# QSPIFlash.net
KiCad netlist of a schematic drawn in Altium Designer
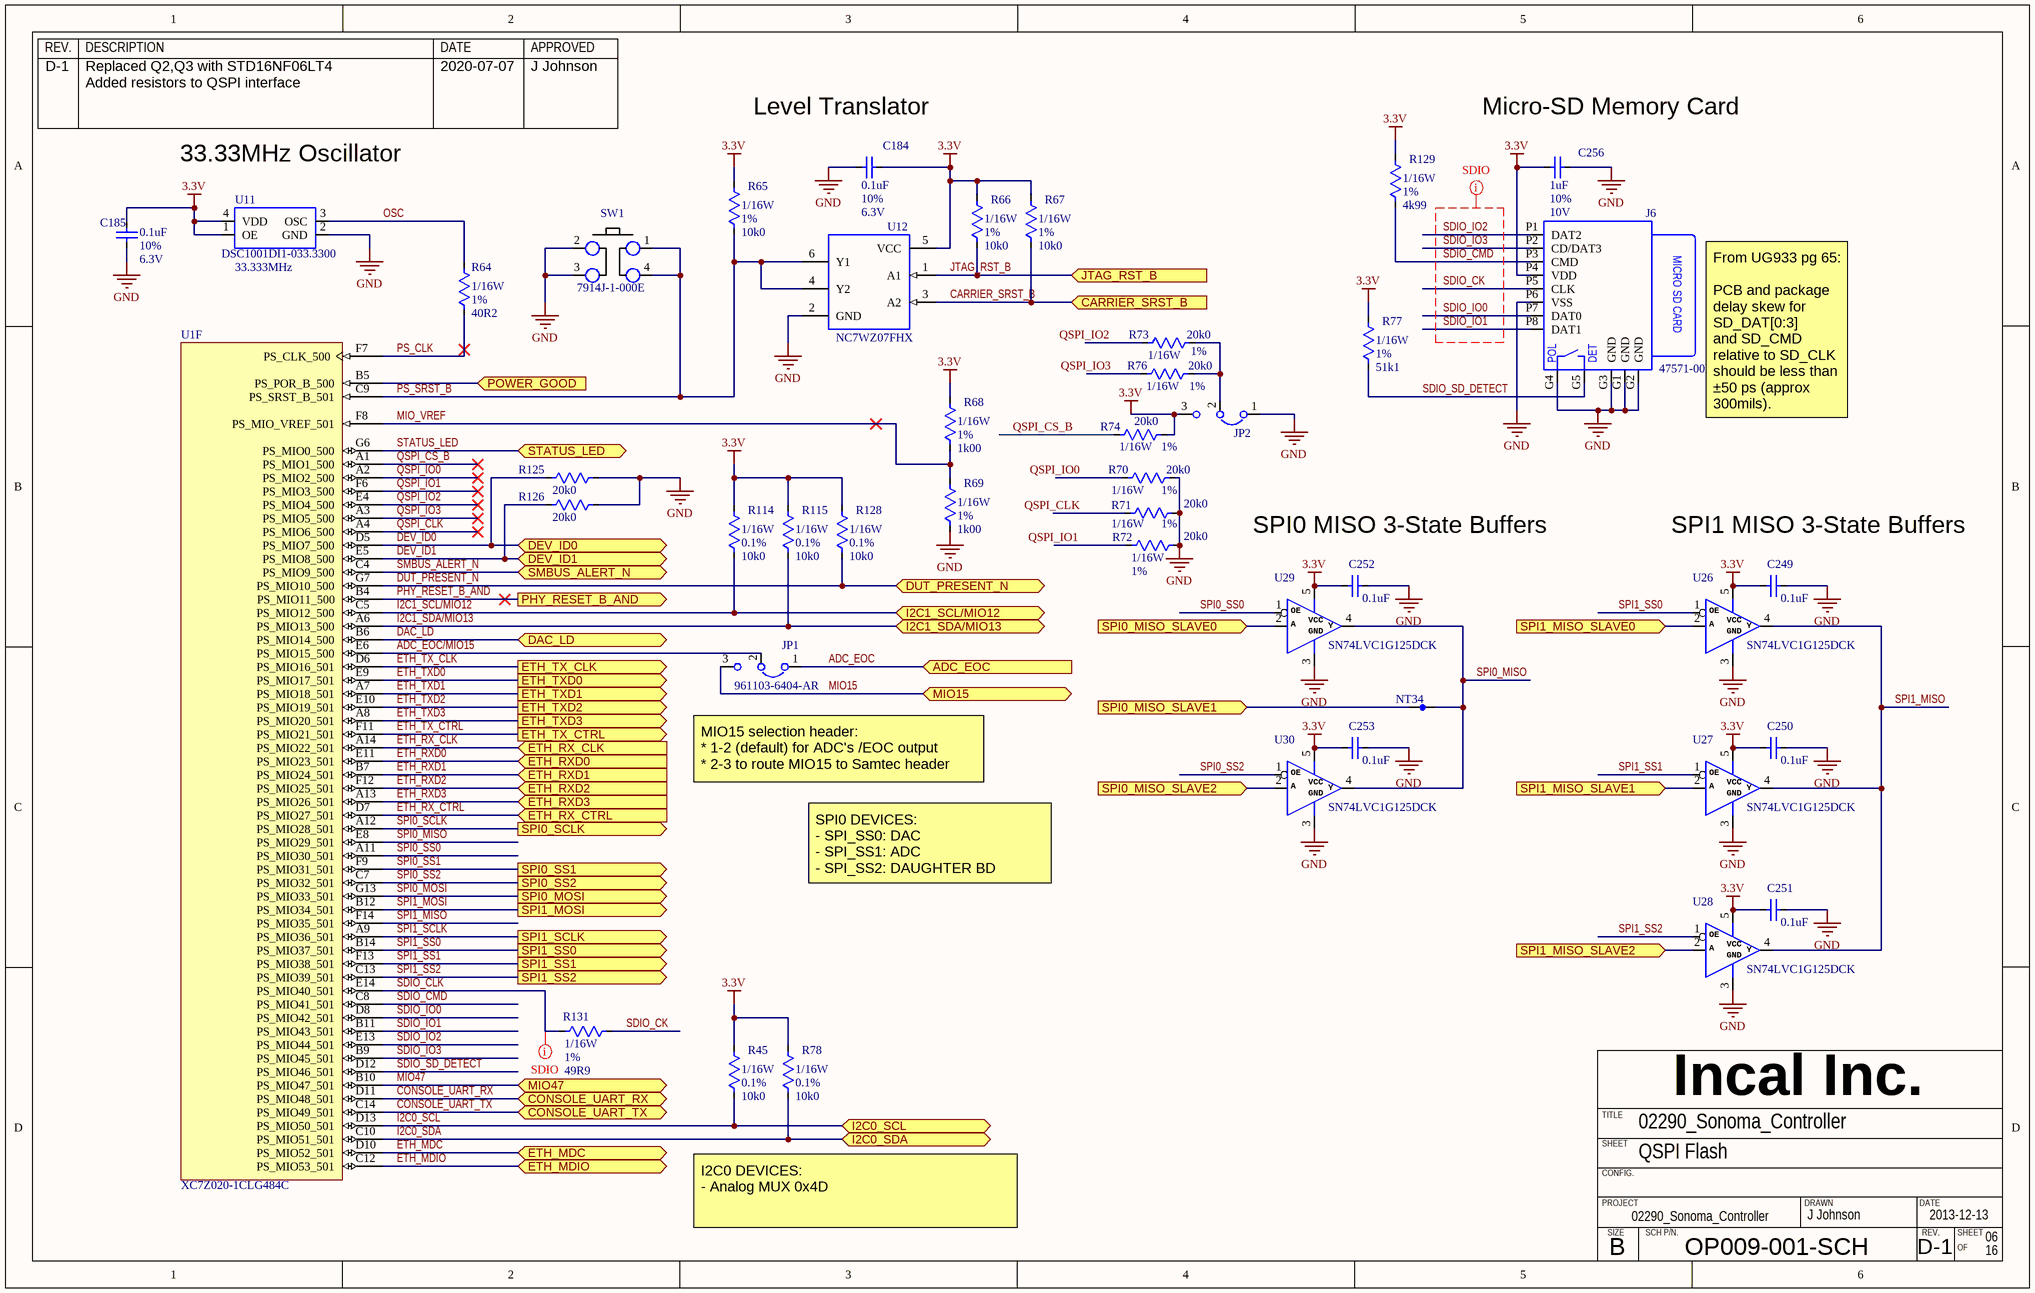
[diagram p0: QSPIFlash.SchDoc]

(export (version "E")
  (design (tool "Eeschema 10.0.6"))
  (components
    (comp (ref "C184")
      (value "0.1uF")
      (footprint "CAPC0603X33N")
      (description "Capacitor ceramic, X5R, 0.1uF, 6.3V, 10%, -55 to +125 C, EIA0201")
      (fields
        (field (name "TOLERANCE") "10%")
        (field (name "VOLTAGE") "6.3V")
        (field (name "Comment") "CAPACITOR_NP_TYPE1")
      )
      (libsource (lib "parts") (part "CAPACITOR_NP_TYPE1"))
    )
    (comp (ref "C185")
      (value "0.1uF")
      (footprint "CAPC0603X33N")
      (description "Capacitor ceramic, X5R, 0.1uF, 6.3V, 10%, -55 to +125 C, EIA0201")
      (fields
        (field (name "TOLERANCE") "10%")
        (field (name "VOLTAGE") "6.3V")
        (field (name "Comment") "CAPACITOR_NP_TYPE1")
      )
      (libsource (lib "parts") (part "CAPACITOR_NP_TYPE1"))
    )
    (comp (ref "C249")
      (value "0.1uF")
      (footprint "CAPC0603X33N")
      (description "Capacitor ceramic, X5R, 0.1uF, 6.3V, 10%, -55 to +125 C, EIA0201")
      (fields (field (name "TOLERANCE") "10%") (field (name "VOLTAGE") "6.3V"))
      (libsource (lib "parts") (part "CAPACITOR_NP_TYPE1"))
    )
    (comp (ref "C250")
      (value "0.1uF")
      (footprint "CAPC0603X33N")
      (description "Capacitor ceramic, X5R, 0.1uF, 6.3V, 10%, -55 to +125 C, EIA0201")
      (fields (field (name "TOLERANCE") "10%") (field (name "VOLTAGE") "6.3V"))
      (libsource (lib "parts") (part "CAPACITOR_NP_TYPE1"))
    )
    (comp (ref "C251")
      (value "0.1uF")
      (footprint "CAPC0603X33N")
      (description "Capacitor ceramic, X5R, 0.1uF, 6.3V, 10%, -55 to +125 C, EIA0201")
      (fields (field (name "TOLERANCE") "10%") (field (name "VOLTAGE") "6.3V"))
      (libsource (lib "parts") (part "CAPACITOR_NP_TYPE1"))
    )
    (comp (ref "C252")
      (value "0.1uF")
      (footprint "CAPC0603X33N")
      (description "Capacitor ceramic, X5R, 0.1uF, 6.3V, 10%, -55 to +125 C, EIA0201")
      (fields (field (name "TOLERANCE") "10%") (field (name "VOLTAGE") "6.3V"))
      (libsource (lib "parts") (part "CAPACITOR_NP_TYPE1"))
    )
    (comp (ref "C253")
      (value "0.1uF")
      (footprint "CAPC0603X33N")
      (description "Capacitor ceramic, X5R, 0.1uF, 6.3V, 10%, -55 to +125 C, EIA0201")
      (fields (field (name "TOLERANCE") "10%") (field (name "VOLTAGE") "6.3V"))
      (libsource (lib "parts") (part "CAPACITOR_NP_TYPE1"))
    )
    (comp (ref "C256")
      (value "1uF")
      (footprint "CAPC1005X33N")
      (description "Capacitor ceramic, X5R, 1uF, 10V, 10%, -55 to +85 C, EIA0402")
      (fields
        (field (name "TOLERANCE") "10%")
        (field (name "VOLTAGE") "10V")
        (field (name "Comment") "CAPACITOR_NP_TYPE1")
      )
      (libsource (lib "parts") (part "CAPACITOR_NP_TYPE1"))
    )
    (comp (ref "J6")
      (value "SD_MICRO_DET1")
      (footprint "47571-0001")
      (description "MicroSD Card Header with Detect, 9 pin, RA, 1.10 mm, SMT, -40 to +85C")
      (fields
        (field (name "POWER") "Pow")
        (field (name "VOLTAGE") "Vol")
        (field (name "MFG PART NUMBER 1") "47571-0001")
      )
      (libsource (lib "parts") (part "SD_MICRO_DET1"))
    )
    (comp (ref "JP1")
      (value "JP_HDR3x1_DEF1")
      (footprint "JMPR3P254_SHUNT12")
      (description "Jumper Header .100'', 3-pin, Default position 1-2, TH")
      (fields
        (field (name "POWER") "Pow")
        (field (name "VOLTAGE") "Vol")
        (field (name "MFG PART NUMBER 1") "961103-6404-AR")
      )
      (libsource (lib "parts") (part "JP_HDR3x1_DEF1"))
    )
    (comp (ref "JP2")
      (value "JP_HDR3x1_DEF1")
      (footprint "JMPR3P254_SHUNT12")
      (description "Jumper Header 100mil, 3-pin, Default position 1-2, TH")
      (libsource (lib "parts") (part "JP_HDR3x1_DEF1"))
    )
    (comp (ref "NT34")
      (value "NET_TIE_1X1")
      (footprint "NET_TIE_1X1")
      (description "Net Tie 1 to 1")
      (libsource (lib "parts") (part "NET_TIE_1X1"))
    )
    (comp (ref "R45")
      (value "10k0")
      (footprint "RESC1005X33N")
      (description "Resistor, 10k0, 1/16W, 0.1%, -50 to +155 C, EIA0402")
      (fields (field (name "VOLTAGE") "50V") (field (name "POWER") "1/16W") (field (name "TOLERANCE") "0.1%"))
      (libsource (lib "parts") (part "RESISTOR_TYPE1"))
    )
    (comp (ref "R64")
      (value "40R2")
      (footprint "RESC1005X33N")
      (description "Resistor, 40R2, 1/16W, 1%, -50 to +155 C, EIA0402, EIA(M)1005")
      (fields (field (name "VOLTAGE") "50V") (field (name "POWER") "1/16W") (field (name "TOLERANCE") "1%"))
      (libsource (lib "parts") (part "RESISTOR_TYPE1"))
    )
    (comp (ref "R65")
      (value "10k0")
      (footprint "RESC1005X33N")
      (description "Resistor, 10k0, 1/16W, 1%, -55 to +155 C, EIA0402")
      (fields (field (name "VOLTAGE") "50V") (field (name "POWER") "1/16W") (field (name "TOLERANCE") "1%"))
      (libsource (lib "parts") (part "RESISTOR_TYPE1"))
    )
    (comp (ref "R66")
      (value "10k0")
      (footprint "RESC1005X33N")
      (description "Resistor, 10k0, 1/16W, 1%, -55 to +155 C, EIA0402")
      (fields (field (name "VOLTAGE") "50V") (field (name "POWER") "1/16W") (field (name "TOLERANCE") "1%"))
      (libsource (lib "parts") (part "RESISTOR_TYPE1"))
    )
    (comp (ref "R67")
      (value "10k0")
      (footprint "RESC1005X33N")
      (description "Resistor, 10k0, 1/16W, 1%, -55 to +155 C, EIA0402")
      (fields (field (name "VOLTAGE") "50V") (field (name "POWER") "1/16W") (field (name "TOLERANCE") "1%"))
      (libsource (lib "parts") (part "RESISTOR_TYPE1"))
    )
    (comp (ref "R68")
      (value "1k00")
      (footprint "RESC1005X33N")
      (description "Resistor, 1k00, 1/16W, 1%, -55 to +155 C, EIA0402")
      (fields (field (name "VOLTAGE") "50V") (field (name "POWER") "1/16W") (field (name "TOLERANCE") "1%"))
      (libsource (lib "parts") (part "RESISTOR_TYPE1"))
    )
    (comp (ref "R69")
      (value "1k00")
      (footprint "RESC1005X33N")
      (description "Resistor, 1k00, 1/16W, 1%, -55 to +155 C, EIA0402")
      (fields (field (name "VOLTAGE") "50V") (field (name "POWER") "1/16W") (field (name "TOLERANCE") "1%"))
      (libsource (lib "parts") (part "RESISTOR_TYPE1"))
    )
    (comp (ref "R70")
      (value "20k0")
      (footprint "RESC1005X33N")
      (description "Resistor, 20k0, 1%, 1/16W, 0402")
      (fields (field (name "VOLTAGE") "50V") (field (name "POWER") "1/16W") (field (name "TOLERANCE") "1%"))
      (libsource (lib "parts") (part "RESISTOR_TYPE1"))
    )
    (comp (ref "R71")
      (value "20k0")
      (footprint "RESC1005X33N")
      (description "Resistor, 20k0, 1%, 1/16W, 0402")
      (fields (field (name "VOLTAGE") "50V") (field (name "POWER") "1/16W") (field (name "TOLERANCE") "1%"))
      (libsource (lib "parts") (part "RESISTOR_TYPE1"))
    )
    (comp (ref "R72")
      (value "20k0")
      (footprint "RESC1005X33N")
      (description "Resistor, 20k0, 1%, 1/16W, 0402")
      (fields (field (name "VOLTAGE") "50V") (field (name "POWER") "1/16W") (field (name "TOLERANCE") "1%"))
      (libsource (lib "parts") (part "RESISTOR_TYPE1"))
    )
    (comp (ref "R73")
      (value "20k0")
      (footprint "RESC1005X33N")
      (description "Resistor, 20k0, 1%, 1/16W, 0402")
      (fields (field (name "VOLTAGE") "50V") (field (name "POWER") "1/16W") (field (name "TOLERANCE") "1%"))
      (libsource (lib "parts") (part "RESISTOR_TYPE1"))
    )
    (comp (ref "R74")
      (value "20k0")
      (footprint "RESC1005X33N")
      (description "Resistor, 20k0, 1%, 1/16W, 0402")
      (fields (field (name "VOLTAGE") "50V") (field (name "POWER") "1/16W") (field (name "TOLERANCE") "1%"))
      (libsource (lib "parts") (part "RESISTOR_TYPE1"))
    )
    (comp (ref "R76")
      (value "20k0")
      (footprint "RESC1005X33N")
      (description "Resistor, 20k0, 1%, 1/16W, 0402")
      (fields (field (name "VOLTAGE") "50V") (field (name "POWER") "1/16W") (field (name "TOLERANCE") "1%"))
      (libsource (lib "parts") (part "RESISTOR_TYPE1"))
    )
    (comp (ref "R77")
      (value "51k1")
      (footprint "RESC1005X33N")
      (description "Resistor, 51k1, 1/16W, 1%, -50 to +155 C, EIA0402, EIA(M)1005")
      (fields (field (name "VOLTAGE") "50V") (field (name "POWER") "1/16W") (field (name "TOLERANCE") "1%"))
      (libsource (lib "parts") (part "RESISTOR_TYPE1"))
    )
    (comp (ref "R78")
      (value "10k0")
      (footprint "RESC1005X33N")
      (description "Resistor, 10k0, 1/16W, 0.1%, -50 to +155 C, EIA0402")
      (fields (field (name "VOLTAGE") "50V") (field (name "POWER") "1/16W") (field (name "TOLERANCE") "0.1%"))
      (libsource (lib "parts") (part "RESISTOR_TYPE1"))
    )
    (comp (ref "R114")
      (value "10k0")
      (footprint "RESC1005X33N")
      (description "Resistor, 10k0, 1/16W, 0.1%, -50 to +155 C, EIA0402")
      (fields (field (name "VOLTAGE") "50V") (field (name "POWER") "1/16W") (field (name "TOLERANCE") "0.1%"))
      (libsource (lib "parts") (part "RESISTOR_TYPE1"))
    )
    (comp (ref "R115")
      (value "10k0")
      (footprint "RESC1005X33N")
      (description "Resistor, 10k0, 1/16W, 0.1%, -50 to +155 C, EIA0402")
      (fields (field (name "VOLTAGE") "50V") (field (name "POWER") "1/16W") (field (name "TOLERANCE") "0.1%"))
      (libsource (lib "parts") (part "RESISTOR_TYPE1"))
    )
    (comp (ref "R125")
      (value "20k0")
      (footprint "RESC1005X33N")
      (description "Resistor, 20k0, 1/16W, 1%, -50 to +155 C, EIA0402, EIA(M)1005")
      (fields (field (name "VOLTAGE") "50V") (field (name "POWER") "1/16W"))
      (libsource (lib "parts") (part "RESISTOR_TYPE1"))
    )
    (comp (ref "R126")
      (value "20k0")
      (footprint "RESC1005X33N")
      (description "Resistor, 20k0, 1/16W, 1%, -50 to +155 C, EIA0402, EIA(M)1005")
      (fields (field (name "VOLTAGE") "50V") (field (name "POWER") "1/16W"))
      (libsource (lib "parts") (part "RESISTOR_TYPE1"))
    )
    (comp (ref "R128")
      (value "10k0")
      (footprint "RESC1005X33N")
      (description "Resistor, 10k0, 1/16W, 0.1%, -50 to +155 C, EIA0402")
      (fields (field (name "VOLTAGE") "50V") (field (name "POWER") "1/16W") (field (name "TOLERANCE") "0.1%"))
      (libsource (lib "parts") (part "RESISTOR_TYPE1"))
    )
    (comp (ref "R129")
      (value "4k99")
      (footprint "RESC1005X33N")
      (description "Resistor, 4k99, 1/16W, 1%, -50 to +155 C, EIA0402, EIA(M)1005")
      (fields (field (name "VOLTAGE") "50V") (field (name "POWER") "1/16W") (field (name "TOLERANCE") "1%"))
      (libsource (lib "parts") (part "RESISTOR_TYPE1"))
    )
    (comp (ref "R131")
      (value "49R9")
      (footprint "RESC1005X33N")
      (description "Resistor, 49R9, 1%, 1/16W, 0402, 0402")
      (fields (field (name "VOLTAGE") "50V") (field (name "POWER") "1/16W") (field (name "TOLERANCE") "1%"))
      (libsource (lib "parts") (part "RESISTOR_TYPE1"))
    )
    (comp (ref "SW1")
      (value "7914J-1-000E")
      (footprint "7914J-1-000E")
      (description "Switch, tactile, 39V, 4mm, -55 to +125 C, SMD")
      (fields (field (name "POWER") "Pow") (field (name "VOLTAGE") "39V"))
      (libsource (lib "parts") (part "SW_SPST_TYPE1"))
    )
    (comp (ref "U1")
      (value "XC7Z020-1CLG484C")
      (footprint "CLG484")
      (description "667 MHz Zynq™-7000 AP SoC, 130 PS I/O, 200 FPGA I/O, 484-Ball BGA, Speed Grade 1, Commercial Grade")
      (fields (field (name "GENERIC PART NUMBER") "XC7Z020") (field (name "MANUFACTURER") "Xilinx"))
      (libsource (lib "parts") (part "XC7Z020-1CLG484C"))
    )
    (comp (ref "U11")
      (value "33.333MHz")
      (footprint "OSCSC165P200X250X85-4N")
      (description "Oscillator, CMOS, 33.333MHz, 50ppm, 1.7V to 3.6V, -40 to +85C, SMT")
      (fields
        (field (name "VOLTAGE") "1.7V to 3.6V")
        (field (name "MFG PART NUMBER 1") "DSC1001DI1-033.3300")
        (field (name "Comment") "OSCILLATOR_TYPE1")
      )
      (libsource (lib "parts") (part "OSCILLATOR_TYPE1"))
    )
    (comp (ref "U12")
      (value "NC7WZ07FHX")
      (footprint "DFN35P100X100X55-6N")
      (description "UHS Dual Buffer, Tiny Logic, 1.65 to 5.5V, -40 to +85 C, 200mW, MicroPak2-6")
      (fields
        (field (name "POWER") "Pow")
        (field (name "VOLTAGE") "1.65 to 5.5V")
        (field (name "MFG PART NUMBER 1") "NC7WZ07FHX")
      )
      (libsource (lib "parts") (part "NC7WZ07FHX"))
    )
    (comp (ref "U26")
      (value "SN74LVC1G125DCK")
      (footprint "SOT65P210X110-5N")
      (description "Tristate buffer, 1.65 to 5.5V, +/- 24mA, -40 to +125 C, 150mW, SC70")
      (fields (field (name "POWER") "150mW") (field (name "VOLTAGE") "1.65 to 5.5V"))
      (libsource (lib "parts") (part "TINY_SCHM_BUF_TRIS_TYPE1"))
    )
    (comp (ref "U27")
      (value "SN74LVC1G125DCK")
      (footprint "SOT65P210X110-5N")
      (description "Tristate buffer, 1.65 to 5.5V, +/- 24mA, -40 to +125 C, 150mW, SC70")
      (fields (field (name "POWER") "150mW") (field (name "VOLTAGE") "1.65 to 5.5V"))
      (libsource (lib "parts") (part "TINY_SCHM_BUF_TRIS_TYPE1"))
    )
    (comp (ref "U28")
      (value "SN74LVC1G125DCK")
      (footprint "SOT65P210X110-5N")
      (description "Tristate buffer, 1.65 to 5.5V, +/- 24mA, -40 to +125 C, 150mW, SC70")
      (fields (field (name "POWER") "150mW") (field (name "VOLTAGE") "1.65 to 5.5V"))
      (libsource (lib "parts") (part "TINY_SCHM_BUF_TRIS_TYPE1"))
    )
    (comp (ref "U29")
      (value "SN74LVC1G125DCK")
      (footprint "SOT65P210X110-5N")
      (description "Tristate buffer, 1.65 to 5.5V, +/- 24mA, -40 to +125 C, 150mW, SC70")
      (fields (field (name "POWER") "150mW") (field (name "VOLTAGE") "1.65 to 5.5V"))
      (libsource (lib "parts") (part "TINY_SCHM_BUF_TRIS_TYPE1"))
    )
    (comp (ref "U30")
      (value "SN74LVC1G125DCK")
      (footprint "SOT65P210X110-5N")
      (description "Tristate buffer, 1.65 to 5.5V, +/- 24mA, -40 to +125 C, 150mW, SC70")
      (fields (field (name "POWER") "150mW") (field (name "VOLTAGE") "1.65 to 5.5V"))
      (libsource (lib "parts") (part "TINY_SCHM_BUF_TRIS_TYPE1"))
    )
  )
  (nets
    (net (code "1") (name "/ADC_EOC") (class "Default") (node (ref "JP1") (pin "1") (pintype "passive")))
    (net (code "2") (name "/ADC_EOC{slash}MIO15") (class "Default")
      (node (ref "JP1") (pin "2") (pintype "passive"))
      (node (ref "U1") (pin "E6") (pinfunction "PS_MIO15_500_E6") (pintype "bidirectional"))
    )
    (net (code "3") (name "/CARRIER_SRST_B") (class "Default")
      (node (ref "R67") (pin "1") (pinfunction "1_1") (pintype "passive"))
      (node (ref "U12") (pin "3") (pinfunction "A2_3") (pintype "input"))
    )
    (net (code "4") (name "/CONSOLE_UART_RX") (class "Default")
      (node (ref "U1") (pin "D11") (pinfunction "PS_MIO48_501_D11") (pintype "bidirectional"))
    )
    (net (code "5") (name "/CONSOLE_UART_TX") (class "Default")
      (node (ref "U1") (pin "C14") (pinfunction "PS_MIO49_501_C14") (pintype "bidirectional"))
    )
    (net (code "6") (name "/DAC_LD") (class "Default")
      (node (ref "U1") (pin "B6") (pinfunction "PS_MIO14_500_B6") (pintype "bidirectional"))
    )
    (net (code "7") (name "/DEV_ID0") (class "Default")
      (node (ref "R125") (pin "1") (pinfunction "1_1") (pintype "passive"))
      (node (ref "U1") (pin "D5") (pinfunction "PS_MIO7_500_D5") (pintype "bidirectional"))
    )
    (net (code "8") (name "/DEV_ID1") (class "Default")
      (node (ref "R126") (pin "1") (pinfunction "1_1") (pintype "passive"))
      (node (ref "U1") (pin "E5") (pinfunction "PS_MIO8_500_E5") (pintype "bidirectional"))
    )
    (net (code "9") (name "/DUT_PRESENT_N") (class "Default")
      (node (ref "R128") (pin "2") (pinfunction "2_2") (pintype "passive"))
      (node (ref "U1") (pin "G7") (pinfunction "PS_MIO10_500_G7") (pintype "bidirectional"))
    )
    (net (code "10") (name "/ETH_MDC") (class "Default")
      (node (ref "U1") (pin "D10") (pinfunction "PS_MIO52_501_D10") (pintype "bidirectional"))
    )
    (net (code "11") (name "/ETH_MDIO") (class "Default")
      (node (ref "U1") (pin "C12") (pinfunction "PS_MIO53_501_C12") (pintype "bidirectional"))
    )
    (net (code "12") (name "/ETH_RXD0") (class "Default")
      (node (ref "U1") (pin "E11") (pinfunction "PS_MIO23_501_E11") (pintype "bidirectional"))
    )
    (net (code "13") (name "/ETH_RXD1") (class "Default")
      (node (ref "U1") (pin "B7") (pinfunction "PS_MIO24_501_B7") (pintype "bidirectional"))
    )
    (net (code "14") (name "/ETH_RXD2") (class "Default")
      (node (ref "U1") (pin "F12") (pinfunction "PS_MIO25_501_F12") (pintype "bidirectional"))
    )
    (net (code "15") (name "/ETH_RXD3") (class "Default")
      (node (ref "U1") (pin "A13") (pinfunction "PS_MIO26_501_A13") (pintype "bidirectional"))
    )
    (net (code "16") (name "/ETH_RX_CLK") (class "Default")
      (node (ref "U1") (pin "A14") (pinfunction "PS_MIO22_501_A14") (pintype "bidirectional"))
    )
    (net (code "17") (name "/ETH_RX_CTRL") (class "Default")
      (node (ref "U1") (pin "D7") (pinfunction "PS_MIO27_501_D7") (pintype "bidirectional"))
    )
    (net (code "18") (name "/ETH_TXD0") (class "Default")
      (node (ref "U1") (pin "E9") (pinfunction "PS_MIO17_501_E9") (pintype "bidirectional"))
    )
    (net (code "19") (name "/ETH_TXD1") (class "Default")
      (node (ref "U1") (pin "A7") (pinfunction "PS_MIO18_501_A7") (pintype "bidirectional"))
    )
    (net (code "20") (name "/ETH_TXD2") (class "Default")
      (node (ref "U1") (pin "E10") (pinfunction "PS_MIO19_501_E10") (pintype "bidirectional"))
    )
    (net (code "21") (name "/ETH_TXD3") (class "Default")
      (node (ref "U1") (pin "A8") (pinfunction "PS_MIO20_501_A8") (pintype "bidirectional"))
    )
    (net (code "22") (name "/ETH_TX_CLK") (class "Default")
      (node (ref "U1") (pin "D6") (pinfunction "PS_MIO16_501_D6") (pintype "bidirectional"))
    )
    (net (code "23") (name "/ETH_TX_CTRL") (class "Default")
      (node (ref "U1") (pin "F11") (pinfunction "PS_MIO21_501_F11") (pintype "bidirectional"))
    )
    (net (code "24") (name "/I2C0_SCL") (class "Default")
      (node (ref "R45") (pin "2") (pinfunction "2_2") (pintype "passive"))
      (node (ref "U1") (pin "D13") (pinfunction "PS_MIO50_501_D13") (pintype "bidirectional"))
    )
    (net (code "25") (name "/I2C0_SDA") (class "Default")
      (node (ref "R78") (pin "2") (pinfunction "2_2") (pintype "passive"))
      (node (ref "U1") (pin "C10") (pinfunction "PS_MIO51_501_C10") (pintype "bidirectional"))
    )
    (net (code "26") (name "/I2C1_SCL{slash}MIO12") (class "Default")
      (node (ref "R114") (pin "2") (pinfunction "2_2") (pintype "passive"))
      (node (ref "U1") (pin "C5") (pinfunction "PS_MIO12_500_C5") (pintype "bidirectional"))
    )
    (net (code "27") (name "/I2C1_SDA{slash}MIO13") (class "Default")
      (node (ref "R115") (pin "2") (pinfunction "2_2") (pintype "passive"))
      (node (ref "U1") (pin "A6") (pinfunction "PS_MIO13_500_A6") (pintype "bidirectional"))
    )
    (net (code "28") (name "/JTAG_RST_B") (class "Default")
      (node (ref "R66") (pin "1") (pinfunction "1_1") (pintype "passive"))
      (node (ref "U12") (pin "1") (pinfunction "A1_1") (pintype "input"))
    )
    (net (code "29") (name "/MIO15") (class "Default") (node (ref "JP1") (pin "3") (pintype "passive")))
    (net (code "30") (name "/MIO47") (class "Default")
      (node (ref "U1") (pin "B10") (pinfunction "PS_MIO47_501_B10") (pintype "bidirectional"))
    )
    (net (code "31") (name "/MIO_VREF") (class "Default")
      (node (ref "R68") (pin "2") (pinfunction "2_2") (pintype "passive"))
      (node (ref "R69") (pin "1") (pinfunction "1_1") (pintype "passive"))
      (node (ref "U1") (pin "F8") (pinfunction "PS_MIO_VREF_501_F8") (pintype "input"))
    )
    (net (code "32") (name "/OSC") (class "Default")
      (node (ref "R64") (pin "1") (pinfunction "1_1") (pintype "passive"))
      (node (ref "U11") (pin "3") (pinfunction "OSC_3") (pintype "passive"))
    )
    (net (code "33") (name "/PHY_RESET_B_AND") (class "Default")
      (node (ref "U1") (pin "B4") (pinfunction "PS_MIO11_500_B4") (pintype "bidirectional"))
    )
    (net (code "34") (name "/POWER_GOOD") (class "Default")
      (node (ref "U1") (pin "B5") (pinfunction "PS_POR_B_500_B5") (pintype "input"))
    )
    (net (code "35") (name "/PS_CLK") (class "Default")
      (node (ref "R64") (pin "2") (pinfunction "2_2") (pintype "passive"))
      (node (ref "U1") (pin "F7") (pinfunction "PS_CLK_500_F7") (pintype "input"))
    )
    (net (code "36") (name "/PS_SRST_B") (class "Default")
      (node (ref "R65") (pin "1") (pinfunction "1_1") (pintype "passive"))
      (node (ref "SW1") (pin "1") (pinfunction "1_1") (pintype "passive"))
      (node (ref "SW1") (pin "4") (pinfunction "4_4") (pintype "passive"))
      (node (ref "U1") (pin "C9") (pinfunction "PS_SRST_B_501_C9") (pintype "input"))
      (node (ref "U12") (pin "4") (pinfunction "Y2_4") (pintype "open_collector"))
      (node (ref "U12") (pin "6") (pinfunction "Y1_6") (pintype "open_collector"))
    )
    (net (code "37") (name "/QSPI_CLK") (class "Default")
      (node (ref "R71") (pin "1") (pinfunction "1_1") (pintype "passive"))
      (node (ref "U1") (pin "A4") (pinfunction "PS_MIO6_500_A4") (pintype "bidirectional"))
    )
    (net (code "38") (name "/QSPI_CS_B") (class "Default")
      (node (ref "R74") (pin "1") (pinfunction "1_1") (pintype "passive"))
      (node (ref "U1") (pin "A1") (pinfunction "PS_MIO1_500_A1") (pintype "bidirectional"))
    )
    (net (code "39") (name "/QSPI_IO0") (class "Default")
      (node (ref "R70") (pin "1") (pinfunction "1_1") (pintype "passive"))
      (node (ref "U1") (pin "A2") (pinfunction "PS_MIO2_500_A2") (pintype "bidirectional"))
    )
    (net (code "40") (name "/QSPI_IO1") (class "Default")
      (node (ref "R72") (pin "1") (pinfunction "1_1") (pintype "passive"))
      (node (ref "U1") (pin "F6") (pinfunction "PS_MIO3_500_F6") (pintype "bidirectional"))
    )
    (net (code "41") (name "/QSPI_IO2") (class "Default")
      (node (ref "R73") (pin "1") (pinfunction "1_1") (pintype "passive"))
      (node (ref "U1") (pin "E4") (pinfunction "PS_MIO4_500_E4") (pintype "bidirectional"))
    )
    (net (code "42") (name "/QSPI_IO3") (class "Default")
      (node (ref "R76") (pin "1") (pinfunction "1_1") (pintype "passive"))
      (node (ref "U1") (pin "A3") (pinfunction "PS_MIO5_500_A3") (pintype "bidirectional"))
    )
    (net (code "43") (name "/SDIO_CK") (class "Default")
      (node (ref "J6") (pin "P5") (pinfunction "CLK_P5") (pintype "passive"))
      (node (ref "R131") (pin "2") (pinfunction "2_2") (pintype "passive"))
    )
    (net (code "44") (name "/SDIO_CLK") (class "Default")
      (node (ref "R131") (pin "1") (pinfunction "1_1") (pintype "passive"))
      (node (ref "U1") (pin "E14") (pinfunction "PS_MIO40_501_E14") (pintype "bidirectional"))
    )
    (net (code "45") (name "/SDIO_CMD") (class "Default")
      (node (ref "J6") (pin "P3") (pinfunction "CMD_P3") (pintype "passive"))
      (node (ref "R129") (pin "2") (pinfunction "2_2") (pintype "passive"))
      (node (ref "U1") (pin "C8") (pinfunction "PS_MIO41_501_C8") (pintype "bidirectional"))
    )
    (net (code "46") (name "/SDIO_IO0") (class "Default")
      (node (ref "J6") (pin "P7") (pinfunction "DAT0_P7") (pintype "passive"))
      (node (ref "U1") (pin "D8") (pinfunction "PS_MIO42_501_D8") (pintype "bidirectional"))
    )
    (net (code "47") (name "/SDIO_IO1") (class "Default")
      (node (ref "J6") (pin "P8") (pinfunction "DAT1_P8") (pintype "passive"))
      (node (ref "U1") (pin "B11") (pinfunction "PS_MIO43_501_B11") (pintype "bidirectional"))
    )
    (net (code "48") (name "/SDIO_IO2") (class "Default")
      (node (ref "J6") (pin "P1") (pinfunction "DAT2_P1") (pintype "passive"))
      (node (ref "U1") (pin "E13") (pinfunction "PS_MIO44_501_E13") (pintype "bidirectional"))
    )
    (net (code "49") (name "/SDIO_IO3") (class "Default")
      (node (ref "J6") (pin "P2") (pinfunction "CD/DAT3_P2") (pintype "passive"))
      (node (ref "U1") (pin "B9") (pinfunction "PS_MIO45_501_B9") (pintype "bidirectional"))
    )
    (net (code "50") (name "/SDIO_SD_DETECT") (class "Default")
      (node (ref "J6") (pin "G5") (pinfunction "DET_G5") (pintype "passive"))
      (node (ref "R77") (pin "2") (pinfunction "2_2") (pintype "passive"))
      (node (ref "U1") (pin "D12") (pinfunction "PS_MIO46_501_D12") (pintype "bidirectional"))
    )
    (net (code "51") (name "/SMBUS_ALERT_N") (class "Default")
      (node (ref "U1") (pin "C4") (pinfunction "PS_MIO9_500_C4") (pintype "bidirectional"))
    )
    (net (code "52") (name "/SPI0_MISO") (class "Default")
      (node (ref "NT34") (pin "2") (pinfunction "2_2") (pintype "passive"))
      (node (ref "U1") (pin "E8") (pinfunction "PS_MIO29_501_E8") (pintype "bidirectional"))
      (node (ref "U29") (pin "4") (pinfunction "Y_4") (pintype "passive"))
      (node (ref "U30") (pin "4") (pinfunction "Y_4") (pintype "passive"))
    )
    (net (code "53") (name "/SPI0_MISO_SLAVE0") (class "Default")
      (node (ref "U29") (pin "2") (pinfunction "A_2") (pintype "passive"))
    )
    (net (code "54") (name "/SPI0_MISO_SLAVE1") (class "Default")
      (node (ref "NT34") (pin "1") (pinfunction "1_1") (pintype "passive"))
    )
    (net (code "55") (name "/SPI0_MISO_SLAVE2") (class "Default")
      (node (ref "U30") (pin "2") (pinfunction "A_2") (pintype "passive"))
    )
    (net (code "56") (name "/SPI0_MOSI") (class "Default")
      (node (ref "U1") (pin "G13") (pinfunction "PS_MIO33_501_G13") (pintype "bidirectional"))
    )
    (net (code "57") (name "/SPI0_SCLK") (class "Default")
      (node (ref "U1") (pin "A12") (pinfunction "PS_MIO28_501_A12") (pintype "bidirectional"))
    )
    (net (code "58") (name "/SPI0_SS0") (class "Default")
      (node (ref "U1") (pin "A11") (pinfunction "PS_MIO30_501_A11") (pintype "bidirectional"))
      (node (ref "U29") (pin "1") (pinfunction "OE_1") (pintype "passive"))
    )
    (net (code "59") (name "/SPI0_SS1") (class "Default")
      (node (ref "U1") (pin "F9") (pinfunction "PS_MIO31_501_F9") (pintype "bidirectional"))
    )
    (net (code "60") (name "/SPI0_SS2") (class "Default")
      (node (ref "U1") (pin "C7") (pinfunction "PS_MIO32_501_C7") (pintype "bidirectional"))
      (node (ref "U30") (pin "1") (pinfunction "OE_1") (pintype "passive"))
    )
    (net (code "61") (name "/SPI1_MISO") (class "Default")
      (node (ref "U1") (pin "F14") (pinfunction "PS_MIO35_501_F14") (pintype "bidirectional"))
      (node (ref "U26") (pin "4") (pinfunction "Y_4") (pintype "passive"))
      (node (ref "U27") (pin "4") (pinfunction "Y_4") (pintype "passive"))
      (node (ref "U28") (pin "4") (pinfunction "Y_4") (pintype "passive"))
    )
    (net (code "62") (name "/SPI1_MISO_SLAVE0") (class "Default")
      (node (ref "U26") (pin "2") (pinfunction "A_2") (pintype "passive"))
    )
    (net (code "63") (name "/SPI1_MISO_SLAVE1") (class "Default")
      (node (ref "U27") (pin "2") (pinfunction "A_2") (pintype "passive"))
    )
    (net (code "64") (name "/SPI1_MISO_SLAVE2") (class "Default")
      (node (ref "U28") (pin "2") (pinfunction "A_2") (pintype "passive"))
    )
    (net (code "65") (name "/SPI1_MOSI") (class "Default")
      (node (ref "U1") (pin "B12") (pinfunction "PS_MIO34_501_B12") (pintype "bidirectional"))
    )
    (net (code "66") (name "/SPI1_SCLK") (class "Default")
      (node (ref "U1") (pin "A9") (pinfunction "PS_MIO36_501_A9") (pintype "bidirectional"))
    )
    (net (code "67") (name "/SPI1_SS0") (class "Default")
      (node (ref "U1") (pin "B14") (pinfunction "PS_MIO37_501_B14") (pintype "bidirectional"))
      (node (ref "U26") (pin "1") (pinfunction "OE_1") (pintype "passive"))
    )
    (net (code "68") (name "/SPI1_SS1") (class "Default")
      (node (ref "U1") (pin "F13") (pinfunction "PS_MIO38_501_F13") (pintype "bidirectional"))
      (node (ref "U27") (pin "1") (pinfunction "OE_1") (pintype "passive"))
    )
    (net (code "69") (name "/SPI1_SS2") (class "Default")
      (node (ref "U1") (pin "C13") (pinfunction "PS_MIO39_501_C13") (pintype "bidirectional"))
      (node (ref "U28") (pin "1") (pinfunction "OE_1") (pintype "passive"))
    )
    (net (code "70") (name "/STATUS_LED") (class "Default")
      (node (ref "U1") (pin "G6") (pinfunction "PS_MIO0_500_G6") (pintype "bidirectional"))
    )
    (net (code "71") (name "3.3V") (class "Default")
      (node (ref "C184") (pin "1") (pinfunction "1_1") (pintype "passive"))
      (node (ref "C185") (pin "1") (pinfunction "1_1") (pintype "passive"))
      (node (ref "C249") (pin "1") (pinfunction "1_1") (pintype "passive"))
      (node (ref "C250") (pin "1") (pinfunction "1_1") (pintype "passive"))
      (node (ref "C251") (pin "1") (pinfunction "1_1") (pintype "passive"))
      (node (ref "C252") (pin "1") (pinfunction "1_1") (pintype "passive"))
      (node (ref "C253") (pin "1") (pinfunction "1_1") (pintype "passive"))
      (node (ref "C256") (pin "1") (pinfunction "1_1") (pintype "passive"))
      (node (ref "J6") (pin "P4") (pinfunction "VDD_P4") (pintype "passive"))
      (node (ref "JP2") (pin "3") (pintype "passive"))
      (node (ref "R114") (pin "1") (pinfunction "1_1") (pintype "passive"))
      (node (ref "R115") (pin "1") (pinfunction "1_1") (pintype "passive"))
      (node (ref "R128") (pin "1") (pinfunction "1_1") (pintype "passive"))
      (node (ref "R129") (pin "1") (pinfunction "1_1") (pintype "passive"))
      (node (ref "R45") (pin "1") (pinfunction "1_1") (pintype "passive"))
      (node (ref "R65") (pin "2") (pinfunction "2_2") (pintype "passive"))
      (node (ref "R66") (pin "2") (pinfunction "2_2") (pintype "passive"))
      (node (ref "R67") (pin "2") (pinfunction "2_2") (pintype "passive"))
      (node (ref "R68") (pin "1") (pinfunction "1_1") (pintype "passive"))
      (node (ref "R74") (pin "2") (pinfunction "2_2") (pintype "passive"))
      (node (ref "R77") (pin "1") (pinfunction "1_1") (pintype "passive"))
      (node (ref "R78") (pin "1") (pinfunction "1_1") (pintype "passive"))
      (node (ref "U11") (pin "1") (pinfunction "OE_1") (pintype "passive"))
      (node (ref "U11") (pin "4") (pinfunction "VDD_4") (pintype "passive"))
      (node (ref "U12") (pin "5") (pinfunction "VCC_5") (pintype "power_in"))
      (node (ref "U26") (pin "5") (pinfunction "VCC_5") (pintype "passive"))
      (node (ref "U27") (pin "5") (pinfunction "VCC_5") (pintype "passive"))
      (node (ref "U28") (pin "5") (pinfunction "VCC_5") (pintype "passive"))
      (node (ref "U29") (pin "5") (pinfunction "VCC_5") (pintype "passive"))
      (node (ref "U30") (pin "5") (pinfunction "VCC_5") (pintype "passive"))
    )
    (net (code "72") (name "GND") (class "Default")
      (node (ref "C184") (pin "2") (pinfunction "2_2") (pintype "passive"))
      (node (ref "C185") (pin "2") (pinfunction "2_2") (pintype "passive"))
      (node (ref "C249") (pin "2") (pinfunction "2_2") (pintype "passive"))
      (node (ref "C250") (pin "2") (pinfunction "2_2") (pintype "passive"))
      (node (ref "C251") (pin "2") (pinfunction "2_2") (pintype "passive"))
      (node (ref "C252") (pin "2") (pinfunction "2_2") (pintype "passive"))
      (node (ref "C253") (pin "2") (pinfunction "2_2") (pintype "passive"))
      (node (ref "C256") (pin "2") (pinfunction "2_2") (pintype "passive"))
      (node (ref "J6") (pin "G1") (pinfunction "GND_G1") (pintype "passive"))
      (node (ref "J6") (pin "G2") (pinfunction "GND_G2") (pintype "passive"))
      (node (ref "J6") (pin "G3") (pinfunction "GND_G3") (pintype "passive"))
      (node (ref "J6") (pin "G4") (pinfunction "POL_G4") (pintype "passive"))
      (node (ref "J6") (pin "P6") (pinfunction "VSS_P6") (pintype "passive"))
      (node (ref "JP2") (pin "1") (pintype "passive"))
      (node (ref "R125") (pin "2") (pinfunction "2_2") (pintype "passive"))
      (node (ref "R126") (pin "2") (pinfunction "2_2") (pintype "passive"))
      (node (ref "R69") (pin "2") (pinfunction "2_2") (pintype "passive"))
      (node (ref "R70") (pin "2") (pinfunction "2_2") (pintype "passive"))
      (node (ref "R71") (pin "2") (pinfunction "2_2") (pintype "passive"))
      (node (ref "R72") (pin "2") (pinfunction "2_2") (pintype "passive"))
      (node (ref "SW1") (pin "2") (pinfunction "2_2") (pintype "passive"))
      (node (ref "SW1") (pin "3") (pinfunction "3_3") (pintype "passive"))
      (node (ref "U11") (pin "2") (pinfunction "GND_2") (pintype "passive"))
      (node (ref "U12") (pin "2") (pinfunction "GND_2") (pintype "power_in"))
      (node (ref "U26") (pin "3") (pinfunction "GND_3") (pintype "passive"))
      (node (ref "U27") (pin "3") (pinfunction "GND_3") (pintype "passive"))
      (node (ref "U28") (pin "3") (pinfunction "GND_3") (pintype "passive"))
      (node (ref "U29") (pin "3") (pinfunction "GND_3") (pintype "passive"))
      (node (ref "U30") (pin "3") (pinfunction "GND_3") (pintype "passive"))
    )
    (net (code "73") (name "Net-(JP2-Pad2)") (class "Default")
      (node (ref "JP2") (pin "2") (pintype "passive"))
      (node (ref "R73") (pin "2") (pinfunction "2_2") (pintype "passive"))
      (node (ref "R76") (pin "2") (pinfunction "2_2") (pintype "passive"))
    )
  )
)
